# eeZeeAudioJack.net
KiCad netlist of a schematic drawn in EAGLE
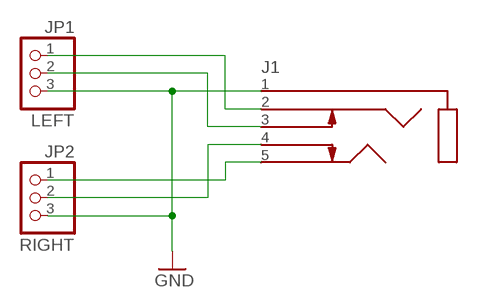
[diagram p0: schematic, sheet 1]

(export (version "E")
  (design (tool "Eeschema 10.0.6"))
  (components
    (comp (ref "J1")
      (value "STEREO_JACK3F07")
      (footprint "eagle-import:3.5AUDIO_3F07")
      (libsource (lib "eagle-import") (part "STEREO_JACK3F07"))
    )
    (comp (ref "JP1")
      (value "LEFT")
      (footprint "eagle-import:1X03-S")
      (libsource (lib "eagle-import") (part "PINHD-1X03_2.54-S"))
    )
    (comp (ref "JP2")
      (value "RIGHT")
      (footprint "eagle-import:1X03-S")
      (libsource (lib "eagle-import") (part "PINHD-1X03_2.54-S"))
    )
  )
  (nets
    (net (code "1") (name "GND") (class "Default")
      (node (ref "J1") (pin "1") (pinfunction "SLEEVE_1") (pintype "bidirectional"))
      (node (ref "JP1") (pin "3") (pinfunction "3_3") (pintype "passive"))
      (node (ref "JP2") (pin "3") (pinfunction "3_3") (pintype "passive"))
    )
    (net (code "2") (name "Net-(J1-RING)") (class "Default")
      (node (ref "J1") (pin "5") (pinfunction "RING_5") (pintype "bidirectional"))
      (node (ref "JP2") (pin "1") (pinfunction "1_1") (pintype "passive"))
    )
    (net (code "3") (name "Net-(J1-RSWITCH)") (class "Default")
      (node (ref "J1") (pin "4") (pinfunction "RSWITCH_4") (pintype "bidirectional"))
      (node (ref "JP2") (pin "2") (pinfunction "2_2") (pintype "passive"))
    )
    (net (code "4") (name "Net-(J1-TIP)") (class "Default")
      (node (ref "J1") (pin "2") (pinfunction "TIP_2") (pintype "bidirectional"))
      (node (ref "JP1") (pin "1") (pinfunction "1_1") (pintype "passive"))
    )
    (net (code "5") (name "Net-(J1-TSWITCH)") (class "Default")
      (node (ref "J1") (pin "3") (pinfunction "TSWITCH_3") (pintype "bidirectional"))
      (node (ref "JP1") (pin "2") (pinfunction "2_2") (pintype "passive"))
    )
  )
)
